# Sheet1.net
KiCad netlist of a schematic drawn in Altium Designer
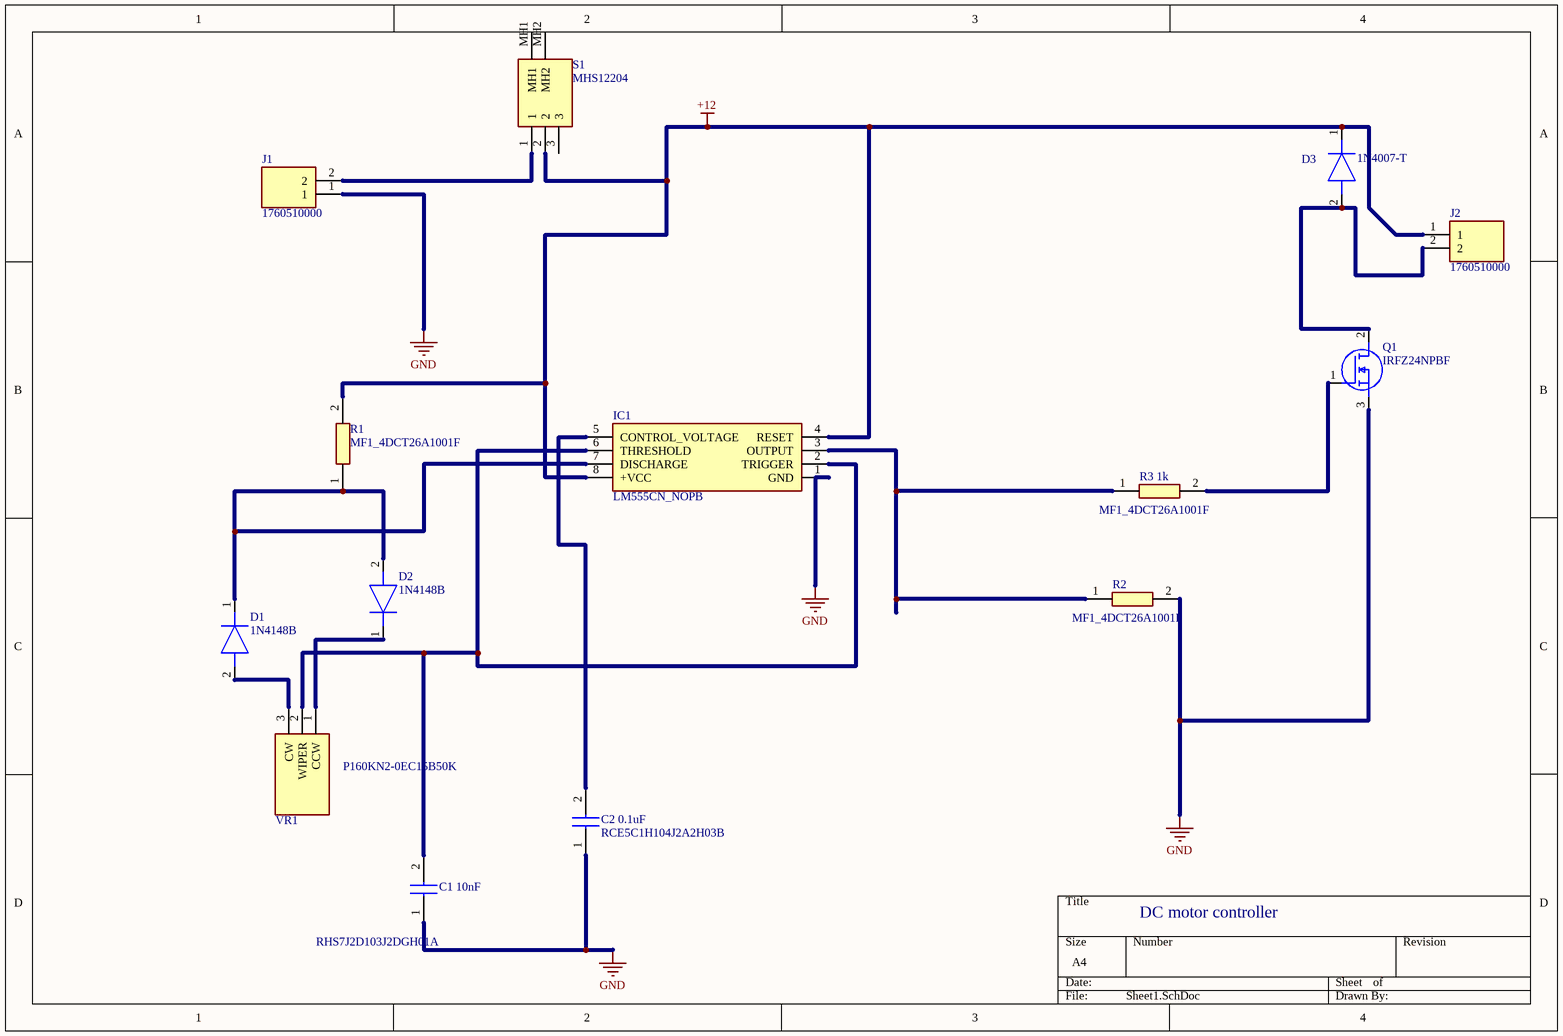
[diagram p0: Sheet1.SchDoc]

(export (version "E")
  (design (tool "Eeschema 10.0.6"))
  (components
    (comp (ref "C1 10nF")
      (value "RHS7J2D103J2DGH01A")
      (footprint "SamacSys:RHS7J2D103J2DGH01A")
      (description "Capacitor")
      (fields (field (name "MOUSER PART NUMBER") "81-RHS7J2D103J2DGH1A"))
      (libsource (lib "*") (part "RHS7J2D103J2DGH01A"))
    )
    (comp (ref "C2 0.1uF")
      (value "RCE5C1H104J2A2H03B")
      (footprint "SamacSys:RCE5C1H104J2A2H03B")
      (description "Capacitor")
      (fields (field (name "MOUSER PART NUMBER") "81-RCE5C1H104J2A2H3B"))
      (libsource (lib "*") (part "RCE5C1H104J2A2H03B"))
    )
    (comp (ref "D1")
      (value "1N4148B")
      (footprint "SamacSys:DIOAD990W55L340D162")
      (description "Diode")
      (libsource (lib "*") (part "1N4148B"))
    )
    (comp (ref "D2")
      (value "1N4148B")
      (footprint "SamacSys:DIOAD990W55L340D162")
      (description "Diode")
      (libsource (lib "*") (part "1N4148B"))
    )
    (comp (ref "D3")
      (value "1N4007-T")
      (footprint "SamacSys:DIOAD1408W86L464D236")
      (description "Diode")
      (libsource (lib "*") (part "1N4007-T"))
    )
    (comp (ref "IC1")
      (value "LM555CN_NOPB")
      (footprint "SamacSys:DIP794W53P254L959H508Q8N")
      (description "Integrated Circuit")
      (fields
        (field (name "MANUFACTURER_PART_NUMBER") "LM555CN/NOPB")
        (field (name "MOUSER PART NUMBER") "926-LM555CN/NOPB")
      )
      (libsource (lib "*") (part "LM555CN_NOPB"))
    )
    (comp (ref "J1")
      (value "1760510000")
      (footprint "SamacSys:1760510000")
      (description "Connector")
      (fields (field (name "MOUSER PART NUMBER") "470-1760510000"))
      (libsource (lib "*") (part "1760510000"))
    )
    (comp (ref "J2")
      (value "1760510000")
      (footprint "SamacSys:1760510000")
      (description "Connector")
      (fields (field (name "MOUSER PART NUMBER") "470-1760510000"))
      (libsource (lib "") (part "1760510000_1"))
    )
    (comp (ref "Q1")
      (value "IRFZ24NPBF")
      (footprint "SamacSys:TO254P469X1042X1967-3P")
      (description "MOSFET (N-Channel)")
      (fields (field (name "MOUSER PART NUMBER") "942-IRFZ24NPBF"))
      (libsource (lib "*") (part "IRFZ24NPBF"))
    )
    (comp (ref "R1")
      (value "MF1_4DCT26A1001F")
      (footprint "SamacSys:RESAD1630W60L710D230")
      (description "Resistor")
      (fields
        (field (name "MANUFACTURER_PART_NUMBER") "MF1/4DCT26A1001F")
        (field (name "MOUSER PART NUMBER") "660-MF1/4DCT26A1001F")
      )
      (libsource (lib "*") (part "MF1_4DCT26A1001F"))
    )
    (comp (ref "R2")
      (value "MF1_4DCT26A1001F")
      (footprint "SamacSys:RESAD1630W60L710D230")
      (description "Resistor")
      (fields
        (field (name "MANUFACTURER_PART_NUMBER") "MF1/4DCT26A1001F")
        (field (name "MOUSER PART NUMBER") "660-MF1/4DCT26A1001F")
      )
      (libsource (lib "") (part "MF1_4DCT26A1001F_1"))
    )
    (comp (ref "R3 1k")
      (value "MF1_4DCT26A1001F")
      (footprint "SamacSys:RESAD1630W60L710D230")
      (description "Resistor")
      (fields
        (field (name "MANUFACTURER_PART_NUMBER") "MF1/4DCT26A1001F")
        (field (name "MOUSER PART NUMBER") "660-MF1/4DCT26A1001F")
      )
      (libsource (lib "") (part "MF1_4DCT26A1001F_1"))
    )
    (comp (ref "S1")
      (value "MHS12204")
      (footprint "SamacSys:MHS12204")
      (description "Switch")
      (fields (field (name "MOUSER PART NUMBER") "506-MHS12204"))
      (libsource (lib "*") (part "MHS12204"))
    )
    (comp (ref "VR1")
      (value "P160KN2-0EC15B50K")
      (footprint "SamacSys:P160KN20EC15B50K")
      (description "Variable Resistor")
      (fields (field (name "MOUSER PART NUMBER") "858-P160KN20EC15B50K"))
      (libsource (lib "*") (part "P160KN2-0EC15B50K"))
    )
  )
  (nets
    (net (code "1") (name "+12") (class "Default")
      (node (ref "D3") (pin "1") (pinfunction "K_1") (pintype "passive"))
      (node (ref "IC1") (pin "4") (pinfunction "RESET_4") (pintype "passive"))
      (node (ref "IC1") (pin "8") (pinfunction "+VCC_8") (pintype "passive"))
      (node (ref "J2") (pin "1") (pinfunction "1_1") (pintype "passive"))
      (node (ref "R1") (pin "2") (pinfunction "2_2") (pintype "passive"))
      (node (ref "S1") (pin "2") (pinfunction "2_2") (pintype "passive"))
    )
    (net (code "2") (name "GND") (class "Default")
      (node (ref "C1 10nF") (pin "1") (pinfunction "1_1") (pintype "passive"))
      (node (ref "C2 0.1uF") (pin "1") (pinfunction "1_1") (pintype "passive"))
      (node (ref "IC1") (pin "1") (pinfunction "GND_1") (pintype "passive"))
      (node (ref "J1") (pin "1") (pinfunction "1_1") (pintype "passive"))
      (node (ref "Q1") (pin "3") (pinfunction "S_3") (pintype "passive"))
      (node (ref "R2") (pin "2") (pinfunction "2_2") (pintype "passive"))
    )
    (net (code "3") (name "Net-(D1-A)") (class "Default")
      (node (ref "D1") (pin "2") (pinfunction "A_2") (pintype "passive"))
      (node (ref "VR1") (pin "3") (pinfunction "CW_3") (pintype "passive"))
    )
    (net (code "4") (name "Net-(D1-K)") (class "Default")
      (node (ref "D1") (pin "1") (pinfunction "K_1") (pintype "passive"))
      (node (ref "D2") (pin "2") (pinfunction "A_2") (pintype "passive"))
      (node (ref "IC1") (pin "7") (pinfunction "DISCHARGE_7") (pintype "passive"))
      (node (ref "R1") (pin "1") (pinfunction "1_1") (pintype "passive"))
    )
    (net (code "5") (name "Net-(D2-K)") (class "Default")
      (node (ref "D2") (pin "1") (pinfunction "K_1") (pintype "passive"))
      (node (ref "VR1") (pin "1") (pinfunction "CCW_1") (pintype "passive"))
    )
    (net (code "6") (name "Net-(D3-A)") (class "Default")
      (node (ref "D3") (pin "2") (pinfunction "A_2") (pintype "passive"))
      (node (ref "J2") (pin "2") (pinfunction "2_2") (pintype "passive"))
      (node (ref "Q1") (pin "2") (pinfunction "D_2") (pintype "passive"))
    )
    (net (code "7") (name "Net-(IC1-CONTROL_VOLTAGE)") (class "Default")
      (node (ref "C2 0.1uF") (pin "2") (pinfunction "2_2") (pintype "passive"))
      (node (ref "IC1") (pin "5") (pinfunction "CONTROL_VOLTAGE_5") (pintype "passive"))
    )
    (net (code "8") (name "Net-(IC1-OUTPUT)") (class "Default")
      (node (ref "IC1") (pin "3") (pinfunction "OUTPUT_3") (pintype "passive"))
      (node (ref "R2") (pin "1") (pinfunction "1_1") (pintype "passive"))
      (node (ref "R3 1k") (pin "1") (pinfunction "1_1") (pintype "passive"))
    )
    (net (code "9") (name "Net-(IC1-THRESHOLD)") (class "Default")
      (node (ref "C1 10nF") (pin "2") (pinfunction "2_2") (pintype "passive"))
      (node (ref "IC1") (pin "2") (pinfunction "TRIGGER_2") (pintype "passive"))
      (node (ref "IC1") (pin "6") (pinfunction "THRESHOLD_6") (pintype "passive"))
      (node (ref "VR1") (pin "2") (pinfunction "WIPER_2") (pintype "passive"))
    )
    (net (code "10") (name "Net-(J1-Pad2)") (class "Default")
      (node (ref "J1") (pin "2") (pinfunction "2_2") (pintype "passive"))
      (node (ref "S1") (pin "1") (pinfunction "1_1") (pintype "passive"))
    )
    (net (code "11") (name "Net-(Q1-G)") (class "Default")
      (node (ref "Q1") (pin "1") (pinfunction "G_1") (pintype "passive"))
      (node (ref "R3 1k") (pin "2") (pinfunction "2_2") (pintype "passive"))
    )
    (net (code "12") (name "unconnected-(S1-Pad3)") (class "Default")
      (node (ref "S1") (pin "3") (pinfunction "3_3") (pintype "passive"))
    )
    (net (code "13") (name "unconnected-(S1-PadMH1)") (class "Default")
      (node (ref "S1") (pin "MH1") (pinfunction "MH1_MH1") (pintype "passive"))
    )
    (net (code "14") (name "unconnected-(S1-PadMH2)") (class "Default")
      (node (ref "S1") (pin "MH2") (pinfunction "MH2_MH2") (pintype "passive"))
    )
  )
)
